# Sheet1.net
KiCad netlist of a schematic drawn in Altium Designer
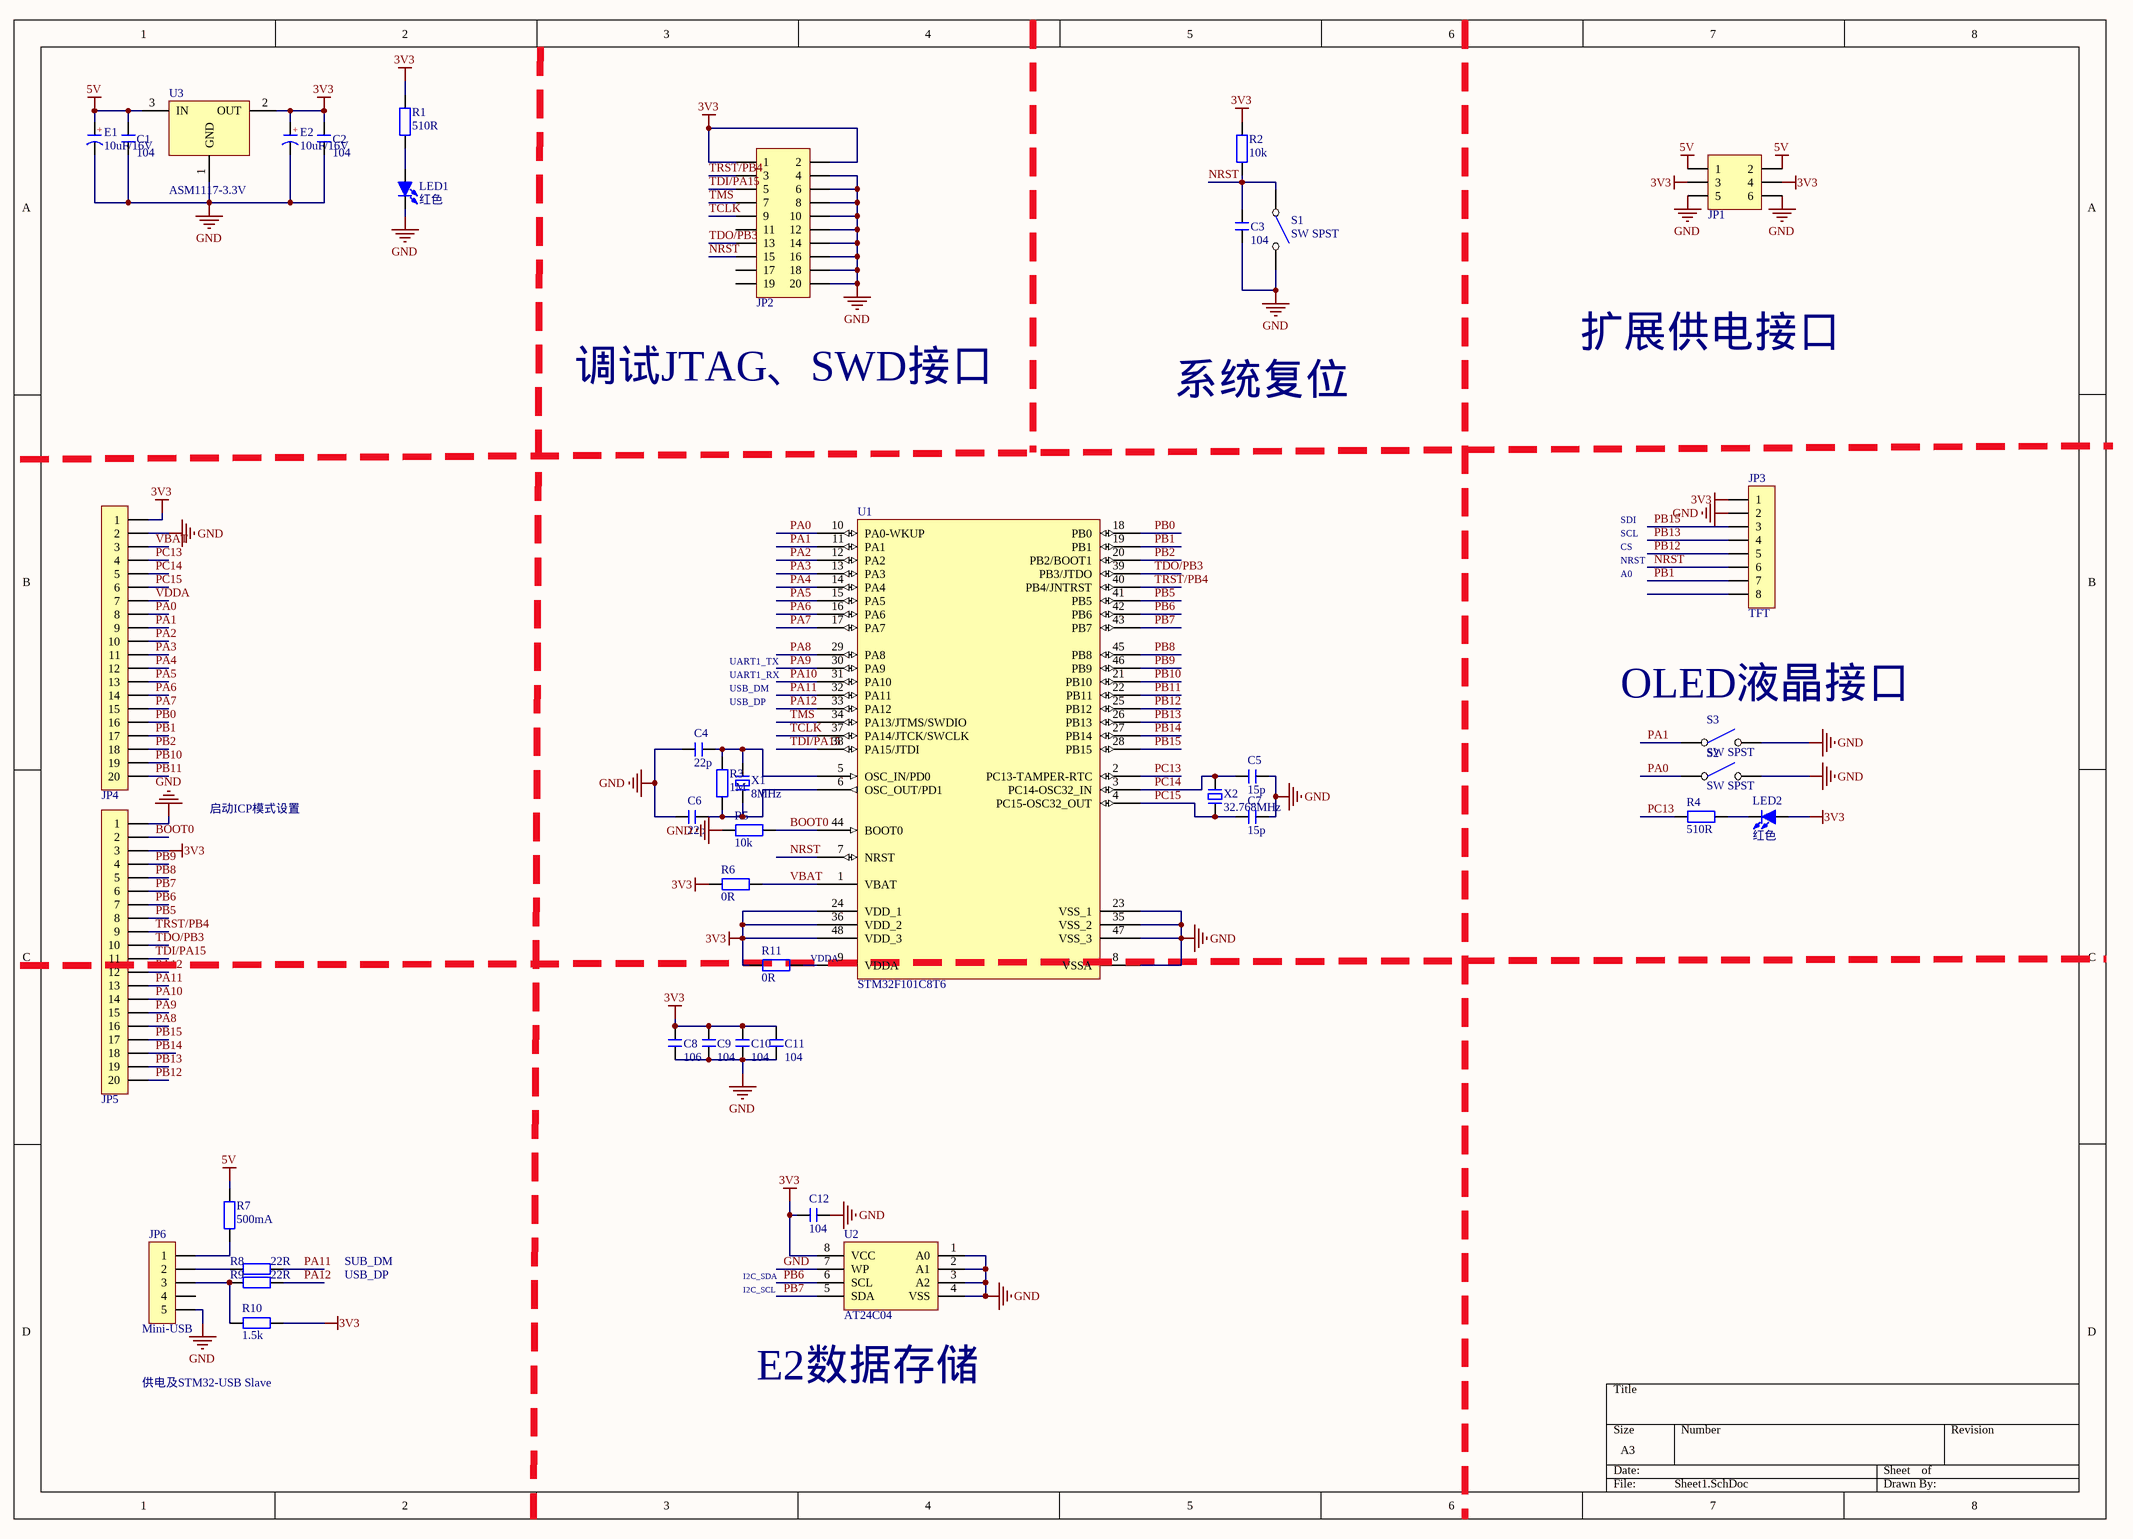
[diagram p0: Sheet1.SchDoc]

(export (version "E")
  (design (tool "Eeschema 10.0.6"))
  (components
    (comp (ref "C1")
      (value "104")
      (footprint "C 0805_M")
      (description "无极性贴片电容")
      (fields (field (name "版权归属") "源创客"))
      (libsource (lib "3.1   - 电阻-电容-电感") (part "C"))
    )
    (comp (ref "C2")
      (value "104")
      (footprint "C 0805_M")
      (description "无极性贴片电容")
      (fields (field (name "版权归属") "源创客"))
      (libsource (lib "3.1   - 电阻-电容-电感") (part "C"))
    )
    (comp (ref "C3")
      (value "104")
      (footprint "C 0805_M")
      (description "无极性贴片电容")
      (fields (field (name "版权归属") "源创客"))
      (libsource (lib "3.1   - 电阻-电容-电感") (part "C"))
    )
    (comp (ref "C4")
      (value "22p")
      (footprint "C 0805_M")
      (description "无极性贴片电容")
      (fields (field (name "版权归属") "源创客"))
      (libsource (lib "3.1   - 电阻-电容-电感") (part "C"))
    )
    (comp (ref "C5")
      (value "15p")
      (footprint "C 0805_M")
      (description "无极性贴片电容")
      (fields (field (name "版权归属") "源创客"))
      (libsource (lib "3.1   - 电阻-电容-电感") (part "C"))
    )
    (comp (ref "C6")
      (value "22p")
      (footprint "C 0805_M")
      (description "无极性贴片电容")
      (fields (field (name "版权归属") "源创客"))
      (libsource (lib "3.1   - 电阻-电容-电感") (part "C"))
    )
    (comp (ref "C7")
      (value "15p")
      (footprint "C 0805_M")
      (description "无极性贴片电容")
      (fields (field (name "版权归属") "源创客"))
      (libsource (lib "3.1   - 电阻-电容-电感") (part "C"))
    )
    (comp (ref "C8")
      (value "106")
      (footprint "C 0805_M")
      (description "无极性贴片电容")
      (fields (field (name "版权归属") "源创客"))
      (libsource (lib "3.1   - 电阻-电容-电感") (part "C"))
    )
    (comp (ref "C9")
      (value "104")
      (footprint "C 0805_M")
      (description "无极性贴片电容")
      (fields (field (name "版权归属") "源创客"))
      (libsource (lib "3.1   - 电阻-电容-电感") (part "C"))
    )
    (comp (ref "C10")
      (value "104")
      (footprint "C 0805_M")
      (description "无极性贴片电容")
      (fields (field (name "版权归属") "源创客"))
      (libsource (lib "3.1   - 电阻-电容-电感") (part "C"))
    )
    (comp (ref "C11")
      (value "104")
      (footprint "C 0805_M")
      (description "无极性贴片电容")
      (fields (field (name "版权归属") "源创客"))
      (libsource (lib "3.1   - 电阻-电容-电感") (part "C"))
    )
    (comp (ref "C12")
      (value "104")
      (footprint "C 0805_M")
      (description "无极性贴片电容")
      (fields (field (name "版权归属") "源创客"))
      (libsource (lib "3.1   - 电阻-电容-电感") (part "C"))
    )
    (comp (ref "E1")
      (value "10uF/16V")
      (footprint "C 0805_M")
      (description "直插电解电容")
      (fields (field (name "版权归属") "源创客"))
      (libsource (lib "3.1   - 电阻-电容-电感") (part "C-CAP"))
    )
    (comp (ref "E2")
      (value "10uF/16V")
      (footprint "C 0805_M")
      (description "直插电解电容")
      (fields (field (name "版权归属") "源创客"))
      (libsource (lib "3.1   - 电阻-电容-电感") (part "C-CAP"))
    )
    (comp (ref "JP1")
      (value "Header3X2")
      (footprint "HDR2.54-LI-2x3P")
      (description "3*2P接插件")
      (fields (field (name "版权归属") "源创客"))
      (libsource (lib "4.3   - 接插件-脚距1.27") (part "Header 3X2"))
    )
    (comp (ref "JP2")
      (value "Header 2X10")
      (footprint "HDR2.54-LI-2x10P")
      (description "10*2P接插件")
      (fields (field (name "版权归属") "源创客"))
      (libsource (lib "4.3   - 接插件-脚距1.27") (part "Header 10X2"))
    )
    (comp (ref "JP3")
      (value "TFT")
      (footprint "HDR2.54-LI-8P")
      (description "8P接插件")
      (fields (field (name "版权归属") "源创客"))
      (libsource (lib "4.3   - 接插件-脚距1.27") (part "Header 8"))
    )
    (comp (ref "JP4")
      (value "HDR-1X20")
      (footprint "HDR2.54-LI-20P")
      (description "20P接插件")
      (fields (field (name "版权归属") "源创客"))
      (libsource (lib "4.3   - 接插件-脚距1.27") (part "Header 20"))
    )
    (comp (ref "JP5")
      (value "HDR-1X20")
      (footprint "HDR2.54-LI-20P")
      (description "20P接插件")
      (fields (field (name "版权归属") "源创客"))
      (libsource (lib "4.3   - 接插件-脚距1.27") (part "Header 20"))
    )
    (comp (ref "JP6")
      (value "Mini-USB")
      (footprint "USB-micro_A")
      (description "5P接插件")
      (fields (field (name "版权归属") "源创客"))
      (libsource (lib "4.3   - 接插件-脚距1.27") (part "Header 5"))
    )
    (comp (ref "LED1")
      (value "红色")
      (footprint "LED 0805Y")
      (description "贴片LED")
      (fields (field (name "版权归属") "源创客"))
      (libsource (lib "9.1   - LED") (part "LED-SMD"))
    )
    (comp (ref "LED2")
      (value "红色")
      (footprint "LED 0805G")
      (description "贴片LED")
      (fields (field (name "版权归属") "源创客"))
      (libsource (lib "9.1   - LED") (part "LED-SMD"))
    )
    (comp (ref "R1")
      (value "510R")
      (footprint "R 0805_M")
      (description "贴片电阻")
      (fields (field (name "版权归属") "源创客"))
      (libsource (lib "3.1   - 电阻-电容-电感") (part "R"))
    )
    (comp (ref "R2")
      (value "10k")
      (footprint "R 0805_M")
      (description "贴片电阻")
      (fields (field (name "版权归属") "源创客"))
      (libsource (lib "3.1   - 电阻-电容-电感") (part "R"))
    )
    (comp (ref "R3")
      (value "1M")
      (footprint "R 0805_M")
      (description "贴片电阻")
      (fields (field (name "版权归属") "源创客"))
      (libsource (lib "3.1   - 电阻-电容-电感") (part "R"))
    )
    (comp (ref "R4")
      (value "510R")
      (footprint "R 0805_M")
      (description "贴片电阻")
      (fields (field (name "版权归属") "源创客"))
      (libsource (lib "3.1   - 电阻-电容-电感") (part "R"))
    )
    (comp (ref "R5")
      (value "10k")
      (footprint "R 0805_M")
      (description "贴片电阻")
      (fields (field (name "版权归属") "源创客"))
      (libsource (lib "3.1   - 电阻-电容-电感") (part "R"))
    )
    (comp (ref "R6")
      (value "0R")
      (footprint "R 0805_M")
      (description "贴片电阻")
      (fields (field (name "版权归属") "源创客"))
      (libsource (lib "3.1   - 电阻-电容-电感") (part "R"))
    )
    (comp (ref "R7")
      (value "500mA")
      (footprint "R 0805_M")
      (description "贴片电阻")
      (fields (field (name "版权归属") "源创客"))
      (libsource (lib "3.1   - 电阻-电容-电感") (part "R"))
    )
    (comp (ref "R8")
      (value "22R")
      (footprint "R 0805_M")
      (description "贴片电阻")
      (fields (field (name "版权归属") "源创客"))
      (libsource (lib "3.1   - 电阻-电容-电感") (part "R"))
    )
    (comp (ref "R9")
      (value "22R")
      (footprint "R 0805_M")
      (description "贴片电阻")
      (fields (field (name "版权归属") "源创客"))
      (libsource (lib "3.1   - 电阻-电容-电感") (part "R"))
    )
    (comp (ref "R10")
      (value "1.5k")
      (footprint "R 0805_M")
      (description "贴片电阻")
      (fields (field (name "版权归属") "源创客"))
      (libsource (lib "3.1   - 电阻-电容-电感") (part "R"))
    )
    (comp (ref "R11")
      (value "0R")
      (footprint "R 0805_M")
      (description "贴片电阻")
      (fields (field (name "版权归属") "源创客"))
      (libsource (lib "3.1   - 电阻-电容-电感") (part "R"))
    )
    (comp (ref "S1") (value "SW SPST") (footprint "KFC DIP-7X7") (libsource (lib "SW开关") (part "SW SPST")))
    (comp (ref "S2") (value "SW SPST") (footprint "TSW SMD-3*6*5") (libsource (lib "SW开关") (part "SW SPST")))
    (comp (ref "S3") (value "SW SPST") (footprint "TSW SMD-3*6*5") (libsource (lib "SW开关") (part "SW SPST")))
    (comp (ref "U1")
      (value "STM32F101C8T6")
      (footprint "LQFP48_M")
      (description "STM32 ARM-based 32-bit MCU with 64 Kbytes Flash, 48-pin LQFP, Industrial Temperature")
      (fields (field (name "PUBLISHER") "Altium Limited"))
      (libsource (lib "ST Microcontroller 32-Bit STM32") (part "STM32F101C8T6"))
    )
    (comp (ref "U2") (value "AT24C04") (footprint "SSOP8_M") (libsource (lib "my") (part "AT24C04")))
    (comp (ref "U3")
      (value "ASM1117-3.3V")
      (footprint "SOT230P700-4L")
      (description "三端可调或固定电压3.3V")
      (libsource (lib "STM32F103C及ASM1117") (part "ASM1117-3.3V"))
    )
    (comp (ref "X1")
      (value "8MHz")
      (footprint "OSC HC-49U")
      (description "2脚无源脚晶振")
      (fields (field (name "版权归属") "源创客"))
      (libsource (lib "10.1 - 保险丝-晶振") (part "XTAL-2P"))
    )
    (comp (ref "X2")
      (value "32.768MHz")
      (footprint "OSC-3x10-WI-A")
      (description "2脚无源脚晶振")
      (fields (field (name "版权归属") "源创客"))
      (libsource (lib "10.1 - 保险丝-晶振") (part "XTAL-2P"))
    )
  )
  (nets
    (net (code "1") (name "/BOOT0") (class "Default")
      (node (ref "JP5") (pin "2") (pinfunction "2_2") (pintype "passive"))
      (node (ref "R5") (pin "1") (pinfunction "1_1") (pintype "passive"))
      (node (ref "U1") (pin "44") (pinfunction "BOOT0_44") (pintype "input"))
    )
    (net (code "2") (name "/NRST") (class "Default")
      (node (ref "C3") (pin "2") (pinfunction "2_2") (pintype "passive"))
      (node (ref "JP2") (pin "15") (pinfunction "15_15") (pintype "passive"))
      (node (ref "JP3") (pin "6") (pinfunction "6_6") (pintype "passive"))
      (node (ref "R2") (pin "1") (pinfunction "1_1") (pintype "passive"))
      (node (ref "S1") (pin "1") (pinfunction "COMMON_1") (pintype "passive"))
      (node (ref "U1") (pin "7") (pinfunction "NRST_7") (pintype "bidirectional"))
    )
    (net (code "3") (name "/PA0") (class "Default")
      (node (ref "JP4") (pin "8") (pinfunction "8_8") (pintype "passive"))
      (node (ref "S2") (pin "1") (pinfunction "COMMON_1") (pintype "passive"))
      (node (ref "U1") (pin "10") (pinfunction "PA0-WKUP_10") (pintype "bidirectional"))
    )
    (net (code "4") (name "/PA1") (class "Default")
      (node (ref "JP4") (pin "9") (pinfunction "9_9") (pintype "passive"))
      (node (ref "S3") (pin "1") (pinfunction "COMMON_1") (pintype "passive"))
      (node (ref "U1") (pin "11") (pinfunction "PA1_11") (pintype "bidirectional"))
    )
    (net (code "5") (name "/PA2") (class "Default")
      (node (ref "JP4") (pin "10") (pinfunction "10_10") (pintype "passive"))
      (node (ref "U1") (pin "12") (pinfunction "PA2_12") (pintype "bidirectional"))
    )
    (net (code "6") (name "/PA3") (class "Default")
      (node (ref "JP4") (pin "11") (pinfunction "11_11") (pintype "passive"))
      (node (ref "U1") (pin "13") (pinfunction "PA3_13") (pintype "bidirectional"))
    )
    (net (code "7") (name "/PA4") (class "Default")
      (node (ref "JP4") (pin "12") (pinfunction "12_12") (pintype "passive"))
      (node (ref "U1") (pin "14") (pinfunction "PA4_14") (pintype "bidirectional"))
    )
    (net (code "8") (name "/PA5") (class "Default")
      (node (ref "JP4") (pin "13") (pinfunction "13_13") (pintype "passive"))
      (node (ref "U1") (pin "15") (pinfunction "PA5_15") (pintype "bidirectional"))
    )
    (net (code "9") (name "/PA6") (class "Default")
      (node (ref "JP4") (pin "14") (pinfunction "14_14") (pintype "passive"))
      (node (ref "U1") (pin "16") (pinfunction "PA6_16") (pintype "bidirectional"))
    )
    (net (code "10") (name "/PA7") (class "Default")
      (node (ref "JP4") (pin "15") (pinfunction "15_15") (pintype "passive"))
      (node (ref "U1") (pin "17") (pinfunction "PA7_17") (pintype "bidirectional"))
    )
    (net (code "11") (name "/PA8") (class "Default")
      (node (ref "JP5") (pin "16") (pinfunction "16_16") (pintype "passive"))
      (node (ref "U1") (pin "29") (pinfunction "PA8_29") (pintype "bidirectional"))
    )
    (net (code "12") (name "/PA9") (class "Default")
      (node (ref "JP5") (pin "15") (pinfunction "15_15") (pintype "passive"))
      (node (ref "U1") (pin "30") (pinfunction "PA9_30") (pintype "bidirectional"))
    )
    (net (code "13") (name "/PA10") (class "Default")
      (node (ref "JP5") (pin "14") (pinfunction "14_14") (pintype "passive"))
      (node (ref "U1") (pin "31") (pinfunction "PA10_31") (pintype "bidirectional"))
    )
    (net (code "14") (name "/PA11") (class "Default")
      (node (ref "JP5") (pin "13") (pinfunction "13_13") (pintype "passive"))
      (node (ref "R8") (pin "1") (pinfunction "1_1") (pintype "passive"))
      (node (ref "U1") (pin "32") (pinfunction "PA11_32") (pintype "bidirectional"))
    )
    (net (code "15") (name "/PA12") (class "Default")
      (node (ref "JP5") (pin "12") (pinfunction "12_12") (pintype "passive"))
      (node (ref "R9") (pin "1") (pinfunction "1_1") (pintype "passive"))
      (node (ref "U1") (pin "33") (pinfunction "PA12_33") (pintype "bidirectional"))
    )
    (net (code "16") (name "/PB0") (class "Default")
      (node (ref "JP4") (pin "16") (pinfunction "16_16") (pintype "passive"))
      (node (ref "U1") (pin "18") (pinfunction "PB0_18") (pintype "bidirectional"))
    )
    (net (code "17") (name "/PB1") (class "Default")
      (node (ref "JP3") (pin "7") (pinfunction "7_7") (pintype "passive"))
      (node (ref "JP4") (pin "17") (pinfunction "17_17") (pintype "passive"))
      (node (ref "U1") (pin "19") (pinfunction "PB1_19") (pintype "bidirectional"))
    )
    (net (code "18") (name "/PB2") (class "Default")
      (node (ref "JP4") (pin "18") (pinfunction "18_18") (pintype "passive"))
      (node (ref "U1") (pin "20") (pinfunction "PB2/BOOT1_20") (pintype "bidirectional"))
    )
    (net (code "19") (name "/PB5") (class "Default")
      (node (ref "JP5") (pin "8") (pinfunction "8_8") (pintype "passive"))
      (node (ref "U1") (pin "41") (pinfunction "PB5_41") (pintype "bidirectional"))
    )
    (net (code "20") (name "/PB6") (class "Default")
      (node (ref "JP5") (pin "7") (pinfunction "7_7") (pintype "passive"))
      (node (ref "U1") (pin "42") (pinfunction "PB6_42") (pintype "bidirectional"))
      (node (ref "U2") (pin "6") (pinfunction "SCL_6") (pintype "passive"))
    )
    (net (code "21") (name "/PB7") (class "Default")
      (node (ref "JP5") (pin "6") (pinfunction "6_6") (pintype "passive"))
      (node (ref "U1") (pin "43") (pinfunction "PB7_43") (pintype "bidirectional"))
      (node (ref "U2") (pin "5") (pinfunction "SDA_5") (pintype "passive"))
    )
    (net (code "22") (name "/PB8") (class "Default")
      (node (ref "JP5") (pin "5") (pinfunction "5_5") (pintype "passive"))
      (node (ref "U1") (pin "45") (pinfunction "PB8_45") (pintype "bidirectional"))
    )
    (net (code "23") (name "/PB9") (class "Default")
      (node (ref "JP5") (pin "4") (pinfunction "4_4") (pintype "passive"))
      (node (ref "U1") (pin "46") (pinfunction "PB9_46") (pintype "bidirectional"))
    )
    (net (code "24") (name "/PB10") (class "Default")
      (node (ref "JP4") (pin "19") (pinfunction "19_19") (pintype "passive"))
      (node (ref "U1") (pin "21") (pinfunction "PB10_21") (pintype "bidirectional"))
    )
    (net (code "25") (name "/PB11") (class "Default")
      (node (ref "JP4") (pin "20") (pinfunction "20_20") (pintype "passive"))
      (node (ref "U1") (pin "22") (pinfunction "PB11_22") (pintype "bidirectional"))
    )
    (net (code "26") (name "/PB12") (class "Default")
      (node (ref "JP3") (pin "5") (pinfunction "5_5") (pintype "passive"))
      (node (ref "JP5") (pin "20") (pinfunction "20_20") (pintype "passive"))
      (node (ref "U1") (pin "25") (pinfunction "PB12_25") (pintype "bidirectional"))
    )
    (net (code "27") (name "/PB13") (class "Default")
      (node (ref "JP3") (pin "4") (pinfunction "4_4") (pintype "passive"))
      (node (ref "JP5") (pin "19") (pinfunction "19_19") (pintype "passive"))
      (node (ref "U1") (pin "26") (pinfunction "PB13_26") (pintype "bidirectional"))
    )
    (net (code "28") (name "/PB14") (class "Default")
      (node (ref "JP5") (pin "18") (pinfunction "18_18") (pintype "passive"))
      (node (ref "U1") (pin "27") (pinfunction "PB14_27") (pintype "bidirectional"))
    )
    (net (code "29") (name "/PB15") (class "Default")
      (node (ref "JP3") (pin "3") (pinfunction "3_3") (pintype "passive"))
      (node (ref "JP5") (pin "17") (pinfunction "17_17") (pintype "passive"))
      (node (ref "U1") (pin "28") (pinfunction "PB15_28") (pintype "bidirectional"))
    )
    (net (code "30") (name "/PC13") (class "Default")
      (node (ref "JP4") (pin "4") (pinfunction "4_4") (pintype "passive"))
      (node (ref "R4") (pin "2") (pinfunction "2_2") (pintype "passive"))
      (node (ref "U1") (pin "2") (pinfunction "PC13-TAMPER-RTC_2") (pintype "bidirectional"))
    )
    (net (code "31") (name "/PC14") (class "Default")
      (node (ref "C5") (pin "2") (pinfunction "2_2") (pintype "passive"))
      (node (ref "JP4") (pin "5") (pinfunction "5_5") (pintype "passive"))
      (node (ref "U1") (pin "3") (pinfunction "PC14-OSC32_IN_3") (pintype "bidirectional"))
      (node (ref "X2") (pin "1") (pinfunction "1_1") (pintype "passive"))
    )
    (net (code "32") (name "/PC15") (class "Default")
      (node (ref "C7") (pin "2") (pinfunction "2_2") (pintype "passive"))
      (node (ref "JP4") (pin "6") (pinfunction "6_6") (pintype "passive"))
      (node (ref "U1") (pin "4") (pinfunction "PC15-OSC32_OUT_4") (pintype "bidirectional"))
      (node (ref "X2") (pin "2") (pinfunction "2_2") (pintype "passive"))
    )
    (net (code "33") (name "/TCLK") (class "Default")
      (node (ref "JP2") (pin "9") (pinfunction "9_9") (pintype "passive"))
      (node (ref "U1") (pin "37") (pinfunction "PA14/JTCK/SWCLK_37") (pintype "bidirectional"))
    )
    (net (code "34") (name "/TDI{slash}PA15") (class "Default")
      (node (ref "JP2") (pin "5") (pinfunction "5_5") (pintype "passive"))
      (node (ref "JP5") (pin "11") (pinfunction "11_11") (pintype "passive"))
      (node (ref "U1") (pin "38") (pinfunction "PA15/JTDI_38") (pintype "bidirectional"))
    )
    (net (code "35") (name "/TDO{slash}PB3") (class "Default")
      (node (ref "JP2") (pin "13") (pinfunction "13_13") (pintype "passive"))
      (node (ref "JP5") (pin "10") (pinfunction "10_10") (pintype "passive"))
      (node (ref "U1") (pin "39") (pinfunction "PB3/JTDO_39") (pintype "bidirectional"))
    )
    (net (code "36") (name "/TMS") (class "Default")
      (node (ref "JP2") (pin "7") (pinfunction "7_7") (pintype "passive"))
      (node (ref "U1") (pin "34") (pinfunction "PA13/JTMS/SWDIO_34") (pintype "bidirectional"))
    )
    (net (code "37") (name "/TRST{slash}PB4") (class "Default")
      (node (ref "JP2") (pin "3") (pinfunction "3_3") (pintype "passive"))
      (node (ref "JP5") (pin "9") (pinfunction "9_9") (pintype "passive"))
      (node (ref "U1") (pin "40") (pinfunction "PB4/JNTRST_40") (pintype "bidirectional"))
    )
    (net (code "42") (name "/VBAT") (class "Default")
      (node (ref "JP4") (pin "3") (pinfunction "3_3") (pintype "passive"))
      (node (ref "R6") (pin "1") (pinfunction "1_1") (pintype "passive"))
      (node (ref "U1") (pin "1") (pinfunction "VBAT_1") (pintype "power_in"))
    )
    (net (code "43") (name "/VDDA") (class "Default")
      (node (ref "JP4") (pin "7") (pinfunction "7_7") (pintype "passive"))
      (node (ref "R11") (pin "1") (pinfunction "1_1") (pintype "passive"))
      (node (ref "U1") (pin "9") (pinfunction "VDDA_9") (pintype "power_in"))
    )
    (net (code "44") (name "3V3") (class "Default")
      (node (ref "C10") (pin "1") (pinfunction "1_1") (pintype "passive"))
      (node (ref "C11") (pin "1") (pinfunction "1_1") (pintype "passive"))
      (node (ref "C12") (pin "1") (pinfunction "1_1") (pintype "passive"))
      (node (ref "C2") (pin "2") (pinfunction "2_2") (pintype "passive"))
      (node (ref "C8") (pin "1") (pinfunction "1_1") (pintype "passive"))
      (node (ref "C9") (pin "1") (pinfunction "1_1") (pintype "passive"))
      (node (ref "E2") (pin "1") (pinfunction "A_1") (pintype "passive"))
      (node (ref "JP1") (pin "3") (pinfunction "3_3") (pintype "passive"))
      (node (ref "JP1") (pin "4") (pinfunction "4_4") (pintype "passive"))
      (node (ref "JP2") (pin "1") (pinfunction "1_1") (pintype "passive"))
      (node (ref "JP2") (pin "2") (pinfunction "2_2") (pintype "passive"))
      (node (ref "JP3") (pin "1") (pinfunction "1_1") (pintype "passive"))
      (node (ref "JP4") (pin "1") (pinfunction "1_1") (pintype "passive"))
      (node (ref "JP5") (pin "3") (pinfunction "3_3") (pintype "passive"))
      (node (ref "LED2") (pin "1") (pinfunction "A_1") (pintype "passive"))
      (node (ref "R1") (pin "2") (pinfunction "2_2") (pintype "passive"))
      (node (ref "R10") (pin "1") (pinfunction "1_1") (pintype "passive"))
      (node (ref "R11") (pin "2") (pinfunction "2_2") (pintype "passive"))
      (node (ref "R2") (pin "2") (pinfunction "2_2") (pintype "passive"))
      (node (ref "R6") (pin "2") (pinfunction "2_2") (pintype "passive"))
      (node (ref "U1") (pin "24") (pinfunction "VDD_1_24") (pintype "power_in"))
      (node (ref "U1") (pin "36") (pinfunction "VDD_2_36") (pintype "power_in"))
      (node (ref "U1") (pin "48") (pinfunction "VDD_3_48") (pintype "power_in"))
      (node (ref "U2") (pin "8") (pinfunction "VCC_8") (pintype "passive"))
      (node (ref "U3") (pin "2") (pinfunction "OUT_2") (pintype "passive"))
    )
    (net (code "45") (name "5V") (class "Default")
      (node (ref "C1") (pin "2") (pinfunction "2_2") (pintype "passive"))
      (node (ref "E1") (pin "1") (pinfunction "A_1") (pintype "passive"))
      (node (ref "JP1") (pin "1") (pinfunction "1_1") (pintype "passive"))
      (node (ref "JP1") (pin "2") (pinfunction "2_2") (pintype "passive"))
      (node (ref "R7") (pin "2") (pinfunction "2_2") (pintype "passive"))
      (node (ref "U3") (pin "3") (pinfunction "IN_3") (pintype "passive"))
    )
    (net (code "46") (name "GND") (class "Default")
      (node (ref "C1") (pin "1") (pinfunction "1_1") (pintype "passive"))
      (node (ref "C10") (pin "2") (pinfunction "2_2") (pintype "passive"))
      (node (ref "C11") (pin "2") (pinfunction "2_2") (pintype "passive"))
      (node (ref "C12") (pin "2") (pinfunction "2_2") (pintype "passive"))
      (node (ref "C2") (pin "1") (pinfunction "1_1") (pintype "passive"))
      (node (ref "C3") (pin "1") (pinfunction "1_1") (pintype "passive"))
      (node (ref "C4") (pin "1") (pinfunction "1_1") (pintype "passive"))
      (node (ref "C5") (pin "1") (pinfunction "1_1") (pintype "passive"))
      (node (ref "C6") (pin "1") (pinfunction "1_1") (pintype "passive"))
      (node (ref "C7") (pin "1") (pinfunction "1_1") (pintype "passive"))
      (node (ref "C8") (pin "2") (pinfunction "2_2") (pintype "passive"))
      (node (ref "C9") (pin "2") (pinfunction "2_2") (pintype "passive"))
      (node (ref "E1") (pin "2") (pinfunction "K_2") (pintype "passive"))
      (node (ref "E2") (pin "2") (pinfunction "K_2") (pintype "passive"))
      (node (ref "JP1") (pin "5") (pinfunction "5_5") (pintype "passive"))
      (node (ref "JP1") (pin "6") (pinfunction "6_6") (pintype "passive"))
      (node (ref "JP2") (pin "10") (pinfunction "10_10") (pintype "passive"))
      (node (ref "JP2") (pin "12") (pinfunction "12_12") (pintype "passive"))
      (node (ref "JP2") (pin "14") (pinfunction "14_14") (pintype "passive"))
      (node (ref "JP2") (pin "16") (pinfunction "16_16") (pintype "passive"))
      (node (ref "JP2") (pin "18") (pinfunction "18_18") (pintype "passive"))
      (node (ref "JP2") (pin "20") (pinfunction "20_20") (pintype "passive"))
      (node (ref "JP2") (pin "4") (pinfunction "4_4") (pintype "passive"))
      (node (ref "JP2") (pin "6") (pinfunction "6_6") (pintype "passive"))
      (node (ref "JP2") (pin "8") (pinfunction "8_8") (pintype "passive"))
      (node (ref "JP3") (pin "2") (pinfunction "2_2") (pintype "passive"))
      (node (ref "JP4") (pin "2") (pinfunction "2_2") (pintype "passive"))
      (node (ref "JP5") (pin "1") (pinfunction "1_1") (pintype "passive"))
      (node (ref "JP6") (pin "5") (pinfunction "5_5") (pintype "passive"))
      (node (ref "LED1") (pin "2") (pinfunction "K_2") (pintype "passive"))
      (node (ref "R5") (pin "2") (pinfunction "2_2") (pintype "passive"))
      (node (ref "S1") (pin "2") (pinfunction "NO_2") (pintype "passive"))
      (node (ref "S2") (pin "2") (pinfunction "NO_2") (pintype "passive"))
      (node (ref "S3") (pin "2") (pinfunction "NO_2") (pintype "passive"))
      (node (ref "U1") (pin "23") (pinfunction "VSS_1_23") (pintype "power_in"))
      (node (ref "U1") (pin "35") (pinfunction "VSS_2_35") (pintype "power_in"))
      (node (ref "U1") (pin "47") (pinfunction "VSS_3_47") (pintype "power_in"))
      (node (ref "U1") (pin "8") (pinfunction "VSSA_8") (pintype "power_in"))
      (node (ref "U2") (pin "1") (pinfunction "A0_1") (pintype "passive"))
      (node (ref "U2") (pin "2") (pinfunction "A1_2") (pintype "passive"))
      (node (ref "U2") (pin "3") (pinfunction "A2_3") (pintype "passive"))
      (node (ref "U2") (pin "4") (pinfunction "VSS_4") (pintype "passive"))
      (node (ref "U2") (pin "7") (pinfunction "WP_7") (pintype "passive"))
      (node (ref "U3") (pin "1") (pinfunction "GND_1") (pintype "passive"))
    )
    (net (code "47") (name "Net-(JP6-Pad1)") (class "Default")
      (node (ref "JP6") (pin "1") (pinfunction "1_1") (pintype "passive"))
      (node (ref "R7") (pin "1") (pinfunction "1_1") (pintype "passive"))
    )
    (net (code "48") (name "Net-(JP6-Pad2)") (class "Default")
      (node (ref "JP6") (pin "2") (pinfunction "2_2") (pintype "passive"))
      (node (ref "R8") (pin "2") (pinfunction "2_2") (pintype "passive"))
    )
    (net (code "49") (name "Net-(JP6-Pad3)") (class "Default")
      (node (ref "JP6") (pin "3") (pinfunction "3_3") (pintype "passive"))
      (node (ref "R10") (pin "2") (pinfunction "2_2") (pintype "passive"))
      (node (ref "R9") (pin "2") (pinfunction "2_2") (pintype "passive"))
    )
    (net (code "50") (name "Net-(LED1-A)") (class "Default")
      (node (ref "LED1") (pin "1") (pinfunction "A_1") (pintype "passive"))
      (node (ref "R1") (pin "1") (pinfunction "1_1") (pintype "passive"))
    )
    (net (code "51") (name "Net-(LED2-K)") (class "Default")
      (node (ref "LED2") (pin "2") (pinfunction "K_2") (pintype "passive"))
      (node (ref "R4") (pin "1") (pinfunction "1_1") (pintype "passive"))
    )
    (net (code "52") (name "Net-(U1-OSC_IN{slash}PD0)") (class "Default")
      (node (ref "C4") (pin "2") (pinfunction "2_2") (pintype "passive"))
      (node (ref "R3") (pin "1") (pinfunction "1_1") (pintype "passive"))
      (node (ref "U1") (pin "5") (pinfunction "OSC_IN/PD0_5") (pintype "input"))
      (node (ref "X1") (pin "2") (pinfunction "2_2") (pintype "passive"))
    )
    (net (code "53") (name "Net-(U1-OSC_OUT{slash}PD1)") (class "Default")
      (node (ref "C6") (pin "2") (pinfunction "2_2") (pintype "passive"))
      (node (ref "R3") (pin "2") (pinfunction "2_2") (pintype "passive"))
      (node (ref "U1") (pin "6") (pinfunction "OSC_OUT/PD1_6") (pintype "output"))
      (node (ref "X1") (pin "1") (pinfunction "1_1") (pintype "passive"))
    )
    (net (code "54") (name "unconnected-(JP2-Pad11)") (class "Default")
      (node (ref "JP2") (pin "11") (pinfunction "11_11") (pintype "passive"))
    )
    (net (code "55") (name "unconnected-(JP2-Pad17)") (class "Default")
      (node (ref "JP2") (pin "17") (pinfunction "17_17") (pintype "passive"))
    )
    (net (code "56") (name "unconnected-(JP2-Pad19)") (class "Default")
      (node (ref "JP2") (pin "19") (pinfunction "19_19") (pintype "passive"))
    )
    (net (code "57") (name "unconnected-(JP3-Pad8)") (class "Default")
      (node (ref "JP3") (pin "8") (pinfunction "8_8") (pintype "passive"))
    )
    (net (code "58") (name "unconnected-(JP6-Pad4)") (class "Default")
      (node (ref "JP6") (pin "4") (pinfunction "4_4") (pintype "passive"))
    )
  )
)
